# LTC2499Test.net
KiCad netlist of a schematic drawn in Altium Designer
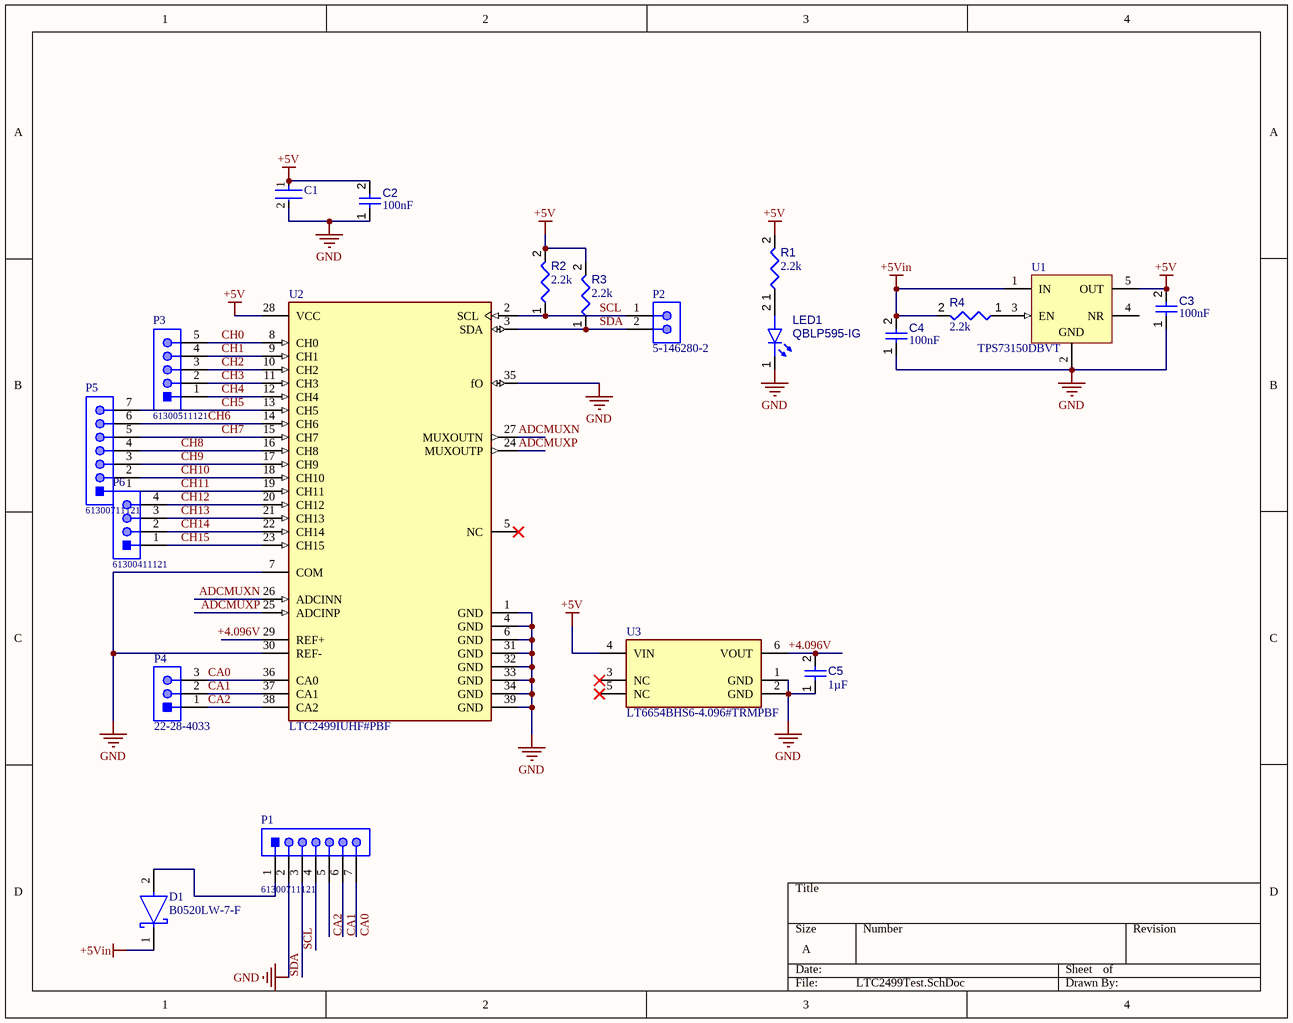
[diagram p0: LTC2499Test.SchDoc]

(export (version "E")
  (design (tool "Eeschema 10.0.6"))
  (components
    (comp (ref "C1")
      (value "GRM21BR60J226ME39L")
      (footprint "FP-GRM21B-0_15-MFG")
      (description "Chip Multilayer Ceramic Capacitors for General Purpose, 0805, 22uF, X5R, 15%, 20%, 6.3V")
      (fields (field (name "VOLTAGE") "6.3V") (field (name "TOLERANCE") "20%"))
      (libsource (lib "Altium Content Vault") (part "b4654b650e69147ec39a6b967a45e02"))
    )
    (comp (ref "C2")
      (value "100nF")
      (footprint "CAPC0402(1005)60_L")
      (description "Chip Capacitor, 100nF +/-20%, 25V, 0402, Thickness 0.6 mm")
      (fields (field (name "TOLERANCE") "10%") (field (name "Comment") "Capacitor 100nF +/-20% 25V 0402"))
      (libsource (lib "Kennesaw Motorsports") (part "CAP-NP-2"))
    )
    (comp (ref "C3")
      (value "100nF")
      (footprint "CAPC0402(1005)60_L")
      (description "Chip Capacitor, 100nF +/-20%, 25V, 0402, Thickness 0.6 mm")
      (fields (field (name "TOLERANCE") "10%") (field (name "Comment") "Capacitor 100nF +/-20% 25V 0402"))
      (libsource (lib "Kennesaw Motorsports") (part "CAP-NP-2"))
    )
    (comp (ref "C4")
      (value "100nF")
      (footprint "CAPC0402(1005)60_L")
      (description "Chip Capacitor, 100nF +/-20%, 25V, 0402, Thickness 0.6 mm")
      (fields (field (name "TOLERANCE") "10%") (field (name "Comment") "Capacitor 100nF +/-20% 25V 0402"))
      (libsource (lib "Kennesaw Motorsports") (part "CAP-NP-2"))
    )
    (comp (ref "C5")
      (value "1µF")
      (footprint "CAPC1608X90X35ML15T15")
      (description "Chip Capacitor, 1 uF, +/- 10%, 16 V, 0603 (1608 Metric)")
      (fields (field (name "TOLERANCE") "10%") (field (name "Comment") "Capacitor 1uF +/- 10% 16V 0603"))
      (libsource (lib "Kennesaw Motorsports") (part "CAP-NP-2"))
    )
    (comp (ref "D1")
      (value "B0520LW-7-F")
      (footprint "FP-SOD123-MFG")
      (description "DIODE SCHOTTKY 20V 500MA SOD123")
      (fields
        (field (name "OCTOPART") "https://octopart.com/b0520lw-7-f-diodes+inc.-325707")
        (field (name "MANUFACTURER") "Diodes Inc.")
      )
      (libsource (lib "Altium Content Vault") (part "1d6ec82d83fb6aee721767c19dac4b9"))
    )
    (comp (ref "LED1")
      (value "QBLP595-IG")
      (footprint "QTB-QBLP595_V")
      (description "Chip LED 0402, Green, 0.02 A, 3.1 to 3.7 V, -40 to 80 degC, 2-Pin SMD, RoHS, Tape and Reel")
      (libsource (lib "Kennesaw Motorsports") (part "LED-KA-2"))
    )
    (comp (ref "P1")
      (value "61300711121")
      (footprint "61300711121")
      (description "THT Vertical Pin Header WR-PHD, Pitch 2.54 mm, Single Row, 7 pins")
      (fields (field (name "MANUFACTURER") "Wurth Elektronik") (field (name "PUBLISHER") "WurthElektronik"))
      (libsource (lib "Altium Content Vault") (part "WE-CN-1P-M-R7"))
    )
    (comp (ref "P2")
      (value "5-146280-2")
      (footprint "TECO-5-146280-2_V")
      (fields (field (name "MANUFACTURER") "TE Connectivity"))
      (libsource (lib "Altium Content Vault") (part "CN-1P-M-R2"))
    )
    (comp (ref "P3")
      (value "61300511121")
      (footprint "61300511121")
      (description "THT Vertical Pin Header WR-PHD, Pitch 2.54 mm, Single Row, 5 pins")
      (fields (field (name "MANUFACTURER") "Wurth Elektronik") (field (name "PUBLISHER") "WurthElektronik"))
      (libsource (lib "Altium Content Vault") (part "WE-CN-1P-M-R5"))
    )
    (comp (ref "P4")
      (value "22-28-4033")
      (footprint "MOLX-22-28-4033_V")
      (description "Male Header, Pitch 2.54 mm, 1 x 3 Position, Height 8.38 mm, Tail Length 3.18 mm, RoHS, Bulk")
      (fields (field (name "MANUFACTURER") "Molex"))
      (libsource (lib "Altium Content Vault") (part "CN-1P-M-R3"))
    )
    (comp (ref "P5")
      (value "61300711121")
      (footprint "61300711121")
      (description "THT Vertical Pin Header WR-PHD, Pitch 2.54 mm, Single Row, 7 pins")
      (fields (field (name "MANUFACTURER") "Wurth Elektronik") (field (name "PUBLISHER") "WurthElektronik"))
      (libsource (lib "") (part "WE-CN-1P-M-R7_1"))
    )
    (comp (ref "P6")
      (value "61300411121")
      (footprint "61300411121")
      (description "THT Vertical Pin Header WR-PHD, Pitch 2.54 mm, Single Row, 4 pins")
      (fields (field (name "MANUFACTURER") "Wurth Elektronik") (field (name "PUBLISHER") "WurthElektronik"))
      (libsource (lib "Altium Content Vault") (part "WE-CN-1P-M-R4"))
    )
    (comp (ref "R1")
      (value "2.2k")
      (footprint "RESC0402(1005)_L")
      (description "Chip Resistor, 2,2 kOhms, +/-5 %, 63 mW, -55 to 155 degC, 0402")
      (fields (field (name "POWER") "63mW") (field (name "TOLERANCE") "5%"))
      (libsource (lib "Kennesaw Motorsports") (part "RES-2"))
    )
    (comp (ref "R2")
      (value "2.2k")
      (footprint "RESC0402(1005)_L")
      (description "Chip Resistor, 2,2 kOhms, +/-5 %, 63 mW, -55 to 155 degC, 0402")
      (fields (field (name "POWER") "63mW") (field (name "TOLERANCE") "5%"))
      (libsource (lib "Kennesaw Motorsports") (part "RES-2"))
    )
    (comp (ref "R3")
      (value "2.2k")
      (footprint "RESC0402(1005)_L")
      (description "Chip Resistor, 2,2 kOhms, +/-5 %, 63 mW, -55 to 155 degC, 0402")
      (fields (field (name "POWER") "63mW") (field (name "TOLERANCE") "5%"))
      (libsource (lib "Kennesaw Motorsports") (part "RES-2"))
    )
    (comp (ref "R4")
      (value "2.2k")
      (footprint "RESC0402(1005)_L")
      (description "Chip Resistor, 2,2 kOhms, +/-5 %, 63 mW, -55 to 155 degC, 0402")
      (fields (field (name "POWER") "63mW") (field (name "TOLERANCE") "5%"))
      (libsource (lib "Kennesaw Motorsports") (part "RES-2"))
    )
    (comp (ref "U1")
      (value "TPS73150DBVT")
      (footprint "DBV0005A_N")
      (fields (field (name "MANUFACTURER") "Texas Instruments"))
      (libsource (lib "Altium Content Vault") (part "TI-TPS79NXX-YYSOT5"))
    )
    (comp (ref "U2")
      (value "LTC2499IUHF#PBF")
      (footprint "FP-UHF-38-05-08-1701-IPC_C")
      (description "IC ADC 24BIT SIGMA-DELTA 38QFN")
      (libsource (lib "Altium Content Vault") (part "078959ea0c6353213d274933d99ad42"))
    )
    (comp (ref "U3")
      (value "LT6654BHS6-4.096#TRMPBF")
      (footprint "FP-S6-6-05-08-1636-IPC_B")
      (description "IC VREF SERIES 0.1% TSOT23-6")
      (fields (field (name "TOLERANCE") "0.1%"))
      (libsource (lib "Altium Content Vault") (part "6204796ecac47dcd8361952bae37060"))
    )
  )
  (nets
    (net (code "1") (name "+5V") (class "Default")
      (node (ref "C1") (pin "1") (pinfunction "1_1") (pintype "passive"))
      (node (ref "C2") (pin "2") (pinfunction "2_2") (pintype "passive"))
      (node (ref "C3") (pin "2") (pinfunction "2_2") (pintype "passive"))
      (node (ref "R1") (pin "2") (pinfunction "2_2") (pintype "passive"))
      (node (ref "R2") (pin "2") (pinfunction "2_2") (pintype "passive"))
      (node (ref "R3") (pin "2") (pinfunction "2_2") (pintype "passive"))
      (node (ref "U1") (pin "5") (pinfunction "OUT_5") (pintype "power_in"))
      (node (ref "U2") (pin "28") (pinfunction "VCC_28") (pintype "power_in"))
      (node (ref "U3") (pin "4") (pinfunction "VIN_4") (pintype "power_in"))
    )
    (net (code "2") (name "+5Vin") (class "Default")
      (node (ref "C4") (pin "2") (pinfunction "2_2") (pintype "passive"))
      (node (ref "D1") (pin "1") (pinfunction "C_1") (pintype "passive"))
      (node (ref "R4") (pin "2") (pinfunction "2_2") (pintype "passive"))
      (node (ref "U1") (pin "1") (pinfunction "IN_1") (pintype "power_in"))
    )
    (net (code "3") (name "/+4.096V") (class "Default")
      (node (ref "C5") (pin "2") (pinfunction "2_2") (pintype "passive"))
      (node (ref "U2") (pin "29") (pinfunction "REF+_29") (pintype "passive"))
      (node (ref "U3") (pin "6") (pinfunction "VOUT_6") (pintype "passive"))
    )
    (net (code "4") (name "/ADCMUXN") (class "Default")
      (node (ref "U2") (pin "26") (pinfunction "ADCINN_26") (pintype "input"))
      (node (ref "U2") (pin "27") (pinfunction "MUXOUTN_27") (pintype "output"))
    )
    (net (code "5") (name "/ADCMUXP") (class "Default")
      (node (ref "U2") (pin "24") (pinfunction "MUXOUTP_24") (pintype "output"))
      (node (ref "U2") (pin "25") (pinfunction "ADCINP_25") (pintype "input"))
    )
    (net (code "6") (name "/CA0") (class "Default")
      (node (ref "P1") (pin "7") (pinfunction "7_7") (pintype "passive"))
      (node (ref "P4") (pin "3") (pinfunction "3_3") (pintype "passive"))
      (node (ref "U2") (pin "36") (pinfunction "CA0_36") (pintype "passive"))
    )
    (net (code "7") (name "/CA1") (class "Default")
      (node (ref "P1") (pin "6") (pinfunction "6_6") (pintype "passive"))
      (node (ref "P4") (pin "2") (pinfunction "2_2") (pintype "passive"))
      (node (ref "U2") (pin "37") (pinfunction "CA1_37") (pintype "passive"))
    )
    (net (code "8") (name "/CA2") (class "Default")
      (node (ref "P1") (pin "5") (pinfunction "5_5") (pintype "passive"))
      (node (ref "P4") (pin "1") (pinfunction "1_1") (pintype "passive"))
      (node (ref "U2") (pin "38") (pinfunction "CA2_38") (pintype "passive"))
    )
    (net (code "9") (name "/CH0") (class "Default")
      (node (ref "P3") (pin "5") (pinfunction "5_5") (pintype "passive"))
      (node (ref "U2") (pin "8") (pinfunction "CH0_8") (pintype "input"))
    )
    (net (code "10") (name "/CH1") (class "Default")
      (node (ref "P3") (pin "4") (pinfunction "4_4") (pintype "passive"))
      (node (ref "U2") (pin "9") (pinfunction "CH1_9") (pintype "input"))
    )
    (net (code "11") (name "/CH2") (class "Default")
      (node (ref "P3") (pin "3") (pinfunction "3_3") (pintype "passive"))
      (node (ref "U2") (pin "10") (pinfunction "CH2_10") (pintype "input"))
    )
    (net (code "12") (name "/CH3") (class "Default")
      (node (ref "P3") (pin "2") (pinfunction "2_2") (pintype "passive"))
      (node (ref "U2") (pin "11") (pinfunction "CH3_11") (pintype "input"))
    )
    (net (code "13") (name "/CH4") (class "Default")
      (node (ref "P3") (pin "1") (pinfunction "1_1") (pintype "passive"))
      (node (ref "U2") (pin "12") (pinfunction "CH4_12") (pintype "input"))
    )
    (net (code "14") (name "/CH5") (class "Default")
      (node (ref "P5") (pin "7") (pinfunction "7_7") (pintype "passive"))
      (node (ref "U2") (pin "13") (pinfunction "CH5_13") (pintype "input"))
    )
    (net (code "15") (name "/CH6") (class "Default")
      (node (ref "P5") (pin "6") (pinfunction "6_6") (pintype "passive"))
      (node (ref "U2") (pin "14") (pinfunction "CH6_14") (pintype "input"))
    )
    (net (code "16") (name "/CH7") (class "Default")
      (node (ref "P5") (pin "5") (pinfunction "5_5") (pintype "passive"))
      (node (ref "U2") (pin "15") (pinfunction "CH7_15") (pintype "input"))
    )
    (net (code "17") (name "/CH8") (class "Default")
      (node (ref "P5") (pin "4") (pinfunction "4_4") (pintype "passive"))
      (node (ref "U2") (pin "16") (pinfunction "CH8_16") (pintype "input"))
    )
    (net (code "18") (name "/CH9") (class "Default")
      (node (ref "P5") (pin "3") (pinfunction "3_3") (pintype "passive"))
      (node (ref "U2") (pin "17") (pinfunction "CH9_17") (pintype "input"))
    )
    (net (code "19") (name "/CH10") (class "Default")
      (node (ref "P5") (pin "2") (pinfunction "2_2") (pintype "passive"))
      (node (ref "U2") (pin "18") (pinfunction "CH10_18") (pintype "input"))
    )
    (net (code "20") (name "/CH11") (class "Default")
      (node (ref "P5") (pin "1") (pinfunction "1_1") (pintype "passive"))
      (node (ref "U2") (pin "19") (pinfunction "CH11_19") (pintype "input"))
    )
    (net (code "21") (name "/CH12") (class "Default")
      (node (ref "P6") (pin "4") (pinfunction "4_4") (pintype "passive"))
      (node (ref "U2") (pin "20") (pinfunction "CH12_20") (pintype "input"))
    )
    (net (code "22") (name "/CH13") (class "Default")
      (node (ref "P6") (pin "3") (pinfunction "3_3") (pintype "passive"))
      (node (ref "U2") (pin "21") (pinfunction "CH13_21") (pintype "input"))
    )
    (net (code "23") (name "/CH14") (class "Default")
      (node (ref "P6") (pin "2") (pinfunction "2_2") (pintype "passive"))
      (node (ref "U2") (pin "22") (pinfunction "CH14_22") (pintype "input"))
    )
    (net (code "24") (name "/CH15") (class "Default")
      (node (ref "P6") (pin "1") (pinfunction "1_1") (pintype "passive"))
      (node (ref "U2") (pin "23") (pinfunction "CH15_23") (pintype "input"))
    )
    (net (code "25") (name "/SCL") (class "Default")
      (node (ref "P1") (pin "4") (pinfunction "4_4") (pintype "passive"))
      (node (ref "P2") (pin "1") (pinfunction "1_1") (pintype "passive"))
      (node (ref "R2") (pin "1") (pinfunction "1_1") (pintype "passive"))
      (node (ref "U2") (pin "2") (pinfunction "SCL_2") (pintype "input"))
    )
    (net (code "26") (name "/SDA") (class "Default")
      (node (ref "P1") (pin "3") (pinfunction "3_3") (pintype "passive"))
      (node (ref "P2") (pin "2") (pinfunction "2_2") (pintype "passive"))
      (node (ref "R3") (pin "1") (pinfunction "1_1") (pintype "passive"))
      (node (ref "U2") (pin "3") (pinfunction "SDA_3") (pintype "bidirectional"))
    )
    (net (code "27") (name "GND") (class "Default")
      (node (ref "C1") (pin "2") (pinfunction "2_2") (pintype "passive"))
      (node (ref "C2") (pin "1") (pinfunction "1_1") (pintype "passive"))
      (node (ref "C3") (pin "1") (pinfunction "1_1") (pintype "passive"))
      (node (ref "C4") (pin "1") (pinfunction "1_1") (pintype "passive"))
      (node (ref "C5") (pin "1") (pinfunction "1_1") (pintype "passive"))
      (node (ref "LED1") (pin "1") (pinfunction "K_1") (pintype "passive"))
      (node (ref "P1") (pin "2") (pinfunction "2_2") (pintype "passive"))
      (node (ref "U1") (pin "2") (pinfunction "GND_2") (pintype "power_in"))
      (node (ref "U2") (pin "1") (pinfunction "GND_1") (pintype "power_in"))
      (node (ref "U2") (pin "30") (pinfunction "REF-_30") (pintype "passive"))
      (node (ref "U2") (pin "31") (pinfunction "GND_31") (pintype "power_in"))
      (node (ref "U2") (pin "32") (pinfunction "GND_32") (pintype "power_in"))
      (node (ref "U2") (pin "33") (pinfunction "GND_33") (pintype "power_in"))
      (node (ref "U2") (pin "34") (pinfunction "GND_34") (pintype "power_in"))
      (node (ref "U2") (pin "35") (pinfunction "fO_35") (pintype "bidirectional"))
      (node (ref "U2") (pin "39") (pinfunction "GND_39") (pintype "power_in"))
      (node (ref "U2") (pin "4") (pinfunction "GND_4") (pintype "power_in"))
      (node (ref "U2") (pin "6") (pinfunction "GND_6") (pintype "power_in"))
      (node (ref "U2") (pin "7") (pinfunction "COM_7") (pintype "passive"))
      (node (ref "U3") (pin "1") (pinfunction "GND_1") (pintype "power_in"))
      (node (ref "U3") (pin "2") (pinfunction "GND_2") (pintype "power_in"))
    )
    (net (code "28") (name "Net-(D1-A)") (class "Default")
      (node (ref "D1") (pin "2") (pinfunction "A_2") (pintype "passive"))
      (node (ref "P1") (pin "1") (pinfunction "1_1") (pintype "passive"))
    )
    (net (code "29") (name "Net-(LED1-A)") (class "Default")
      (node (ref "LED1") (pin "2") (pinfunction "A_2") (pintype "passive"))
      (node (ref "R1") (pin "1") (pinfunction "1_1") (pintype "passive"))
    )
    (net (code "30") (name "Net-(U1-EN)") (class "Default")
      (node (ref "R4") (pin "1") (pinfunction "1_1") (pintype "passive"))
      (node (ref "U1") (pin "3") (pinfunction "EN_3") (pintype "input"))
    )
    (net (code "31") (name "unconnected-(U1-NR-Pad4)") (class "Default")
      (node (ref "U1") (pin "4") (pinfunction "NR_4") (pintype "passive"))
    )
    (net (code "32") (name "unconnected-(U2-NC-Pad5)") (class "Default")
      (node (ref "U2") (pin "5") (pinfunction "NC_5") (pintype "passive+no_connect"))
    )
    (net (code "33") (name "unconnected-(U3-NC-Pad3)") (class "Default")
      (node (ref "U3") (pin "3") (pinfunction "NC_3") (pintype "passive+no_connect"))
    )
    (net (code "34") (name "unconnected-(U3-NC-Pad5)") (class "Default")
      (node (ref "U3") (pin "5") (pinfunction "NC_5") (pintype "passive+no_connect"))
    )
  )
)
